# 12v-driver.net
KiCad netlist of a schematic drawn in EAGLE
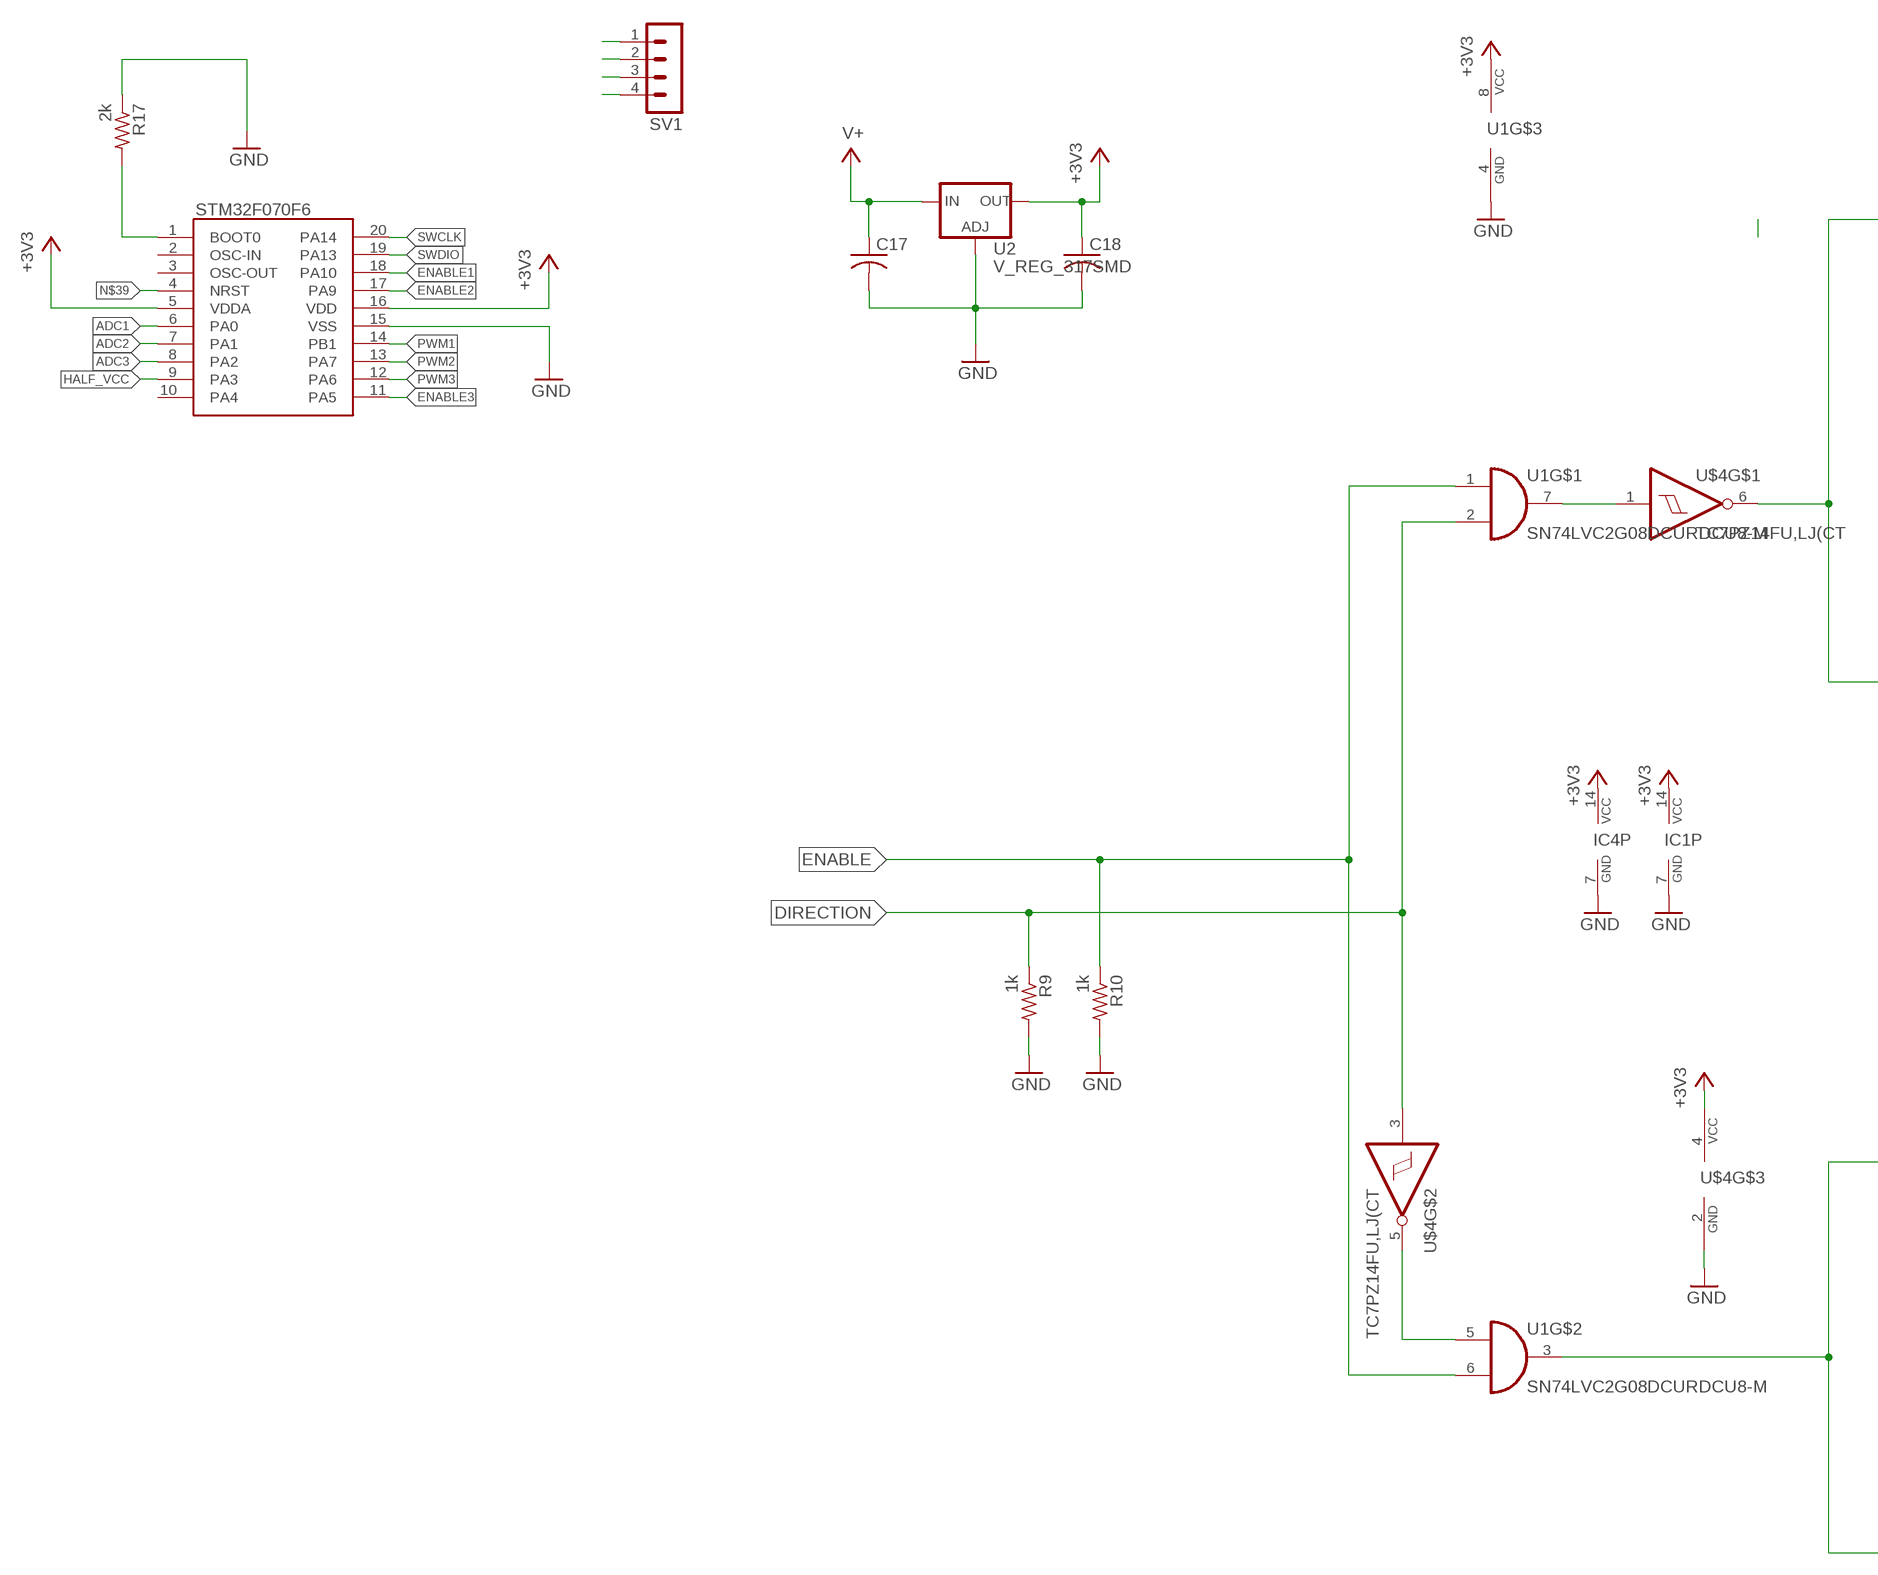
[diagram p0: schematic, sheet 1, part 1 of 2]
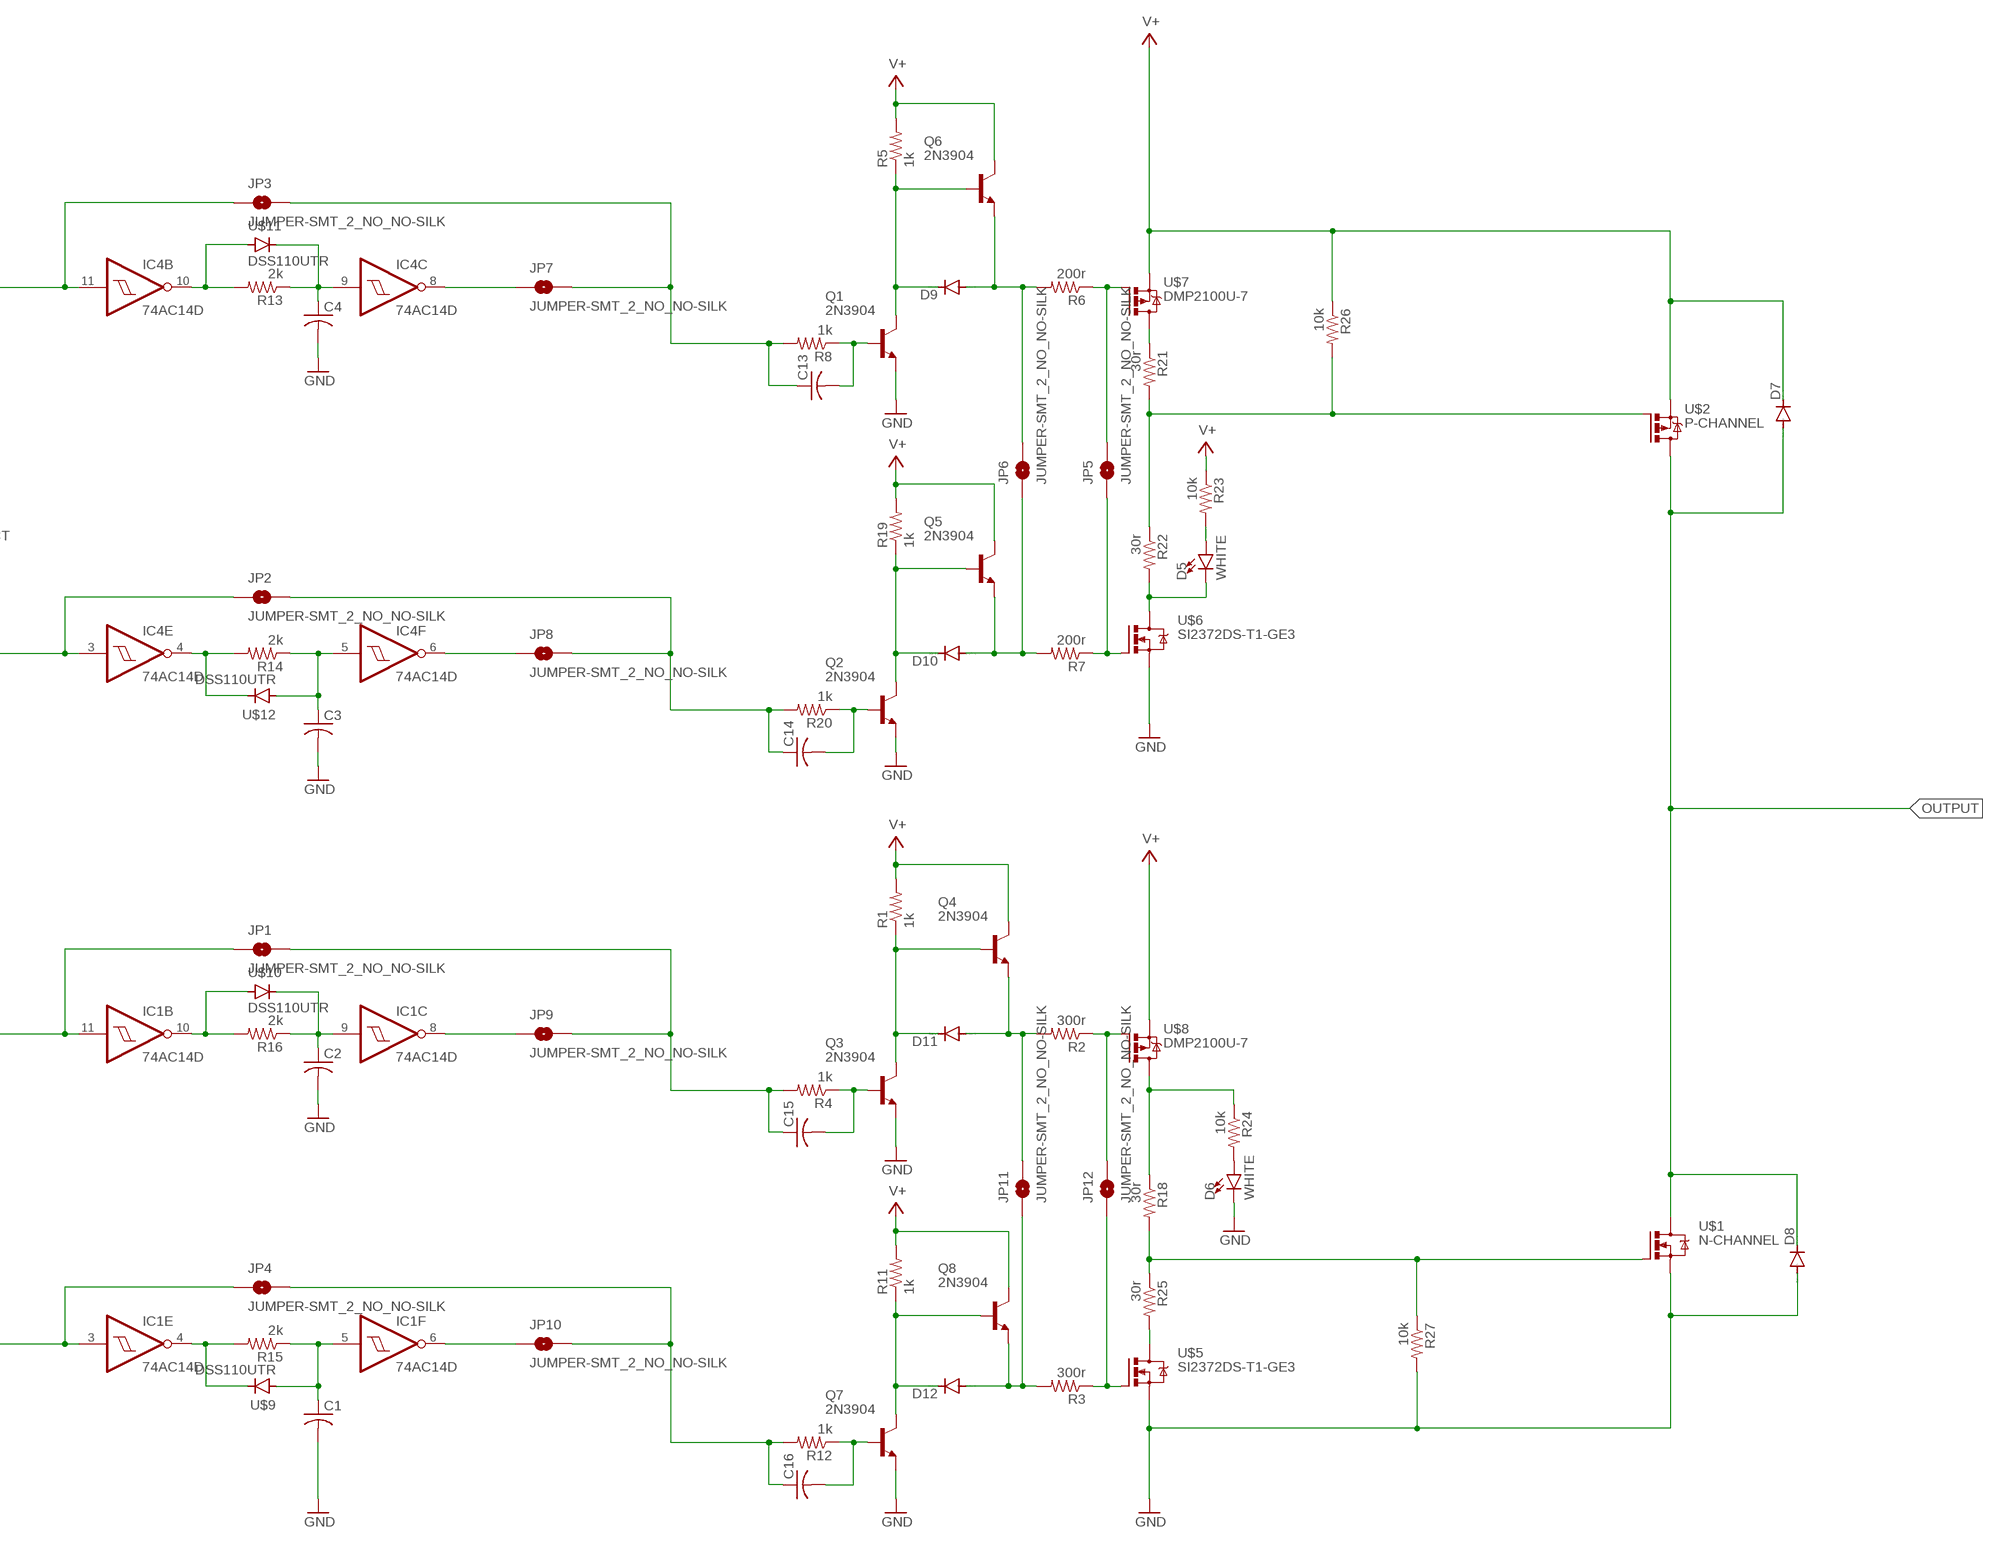
[diagram p1: schematic, sheet 1, part 2 of 2]

(export (version "E")
  (design (tool "Eeschema 10.0.6"))
  (components
    (comp (ref "C1")
      (value "C-USC0603")
      (footprint "eagle-import:C0603")
      (libsource (lib "eagle-import") (part "C-USC0603"))
    )
    (comp (ref "C2")
      (value "C-USC0603")
      (footprint "eagle-import:C0603")
      (libsource (lib "eagle-import") (part "C-USC0603"))
    )
    (comp (ref "C3")
      (value "C-USC0603")
      (footprint "eagle-import:C0603")
      (libsource (lib "eagle-import") (part "C-USC0603"))
    )
    (comp (ref "C4")
      (value "C-USC0603")
      (footprint "eagle-import:C0603")
      (libsource (lib "eagle-import") (part "C-USC0603"))
    )
    (comp (ref "C13")
      (value "C-USC0603")
      (footprint "eagle-import:C0603")
      (libsource (lib "eagle-import") (part "C-USC0603"))
    )
    (comp (ref "C14")
      (value "C-USC0603")
      (footprint "eagle-import:C0603")
      (libsource (lib "eagle-import") (part "C-USC0603"))
    )
    (comp (ref "C15")
      (value "C-USC0603")
      (footprint "eagle-import:C0603")
      (libsource (lib "eagle-import") (part "C-USC0603"))
    )
    (comp (ref "C16")
      (value "C-USC0603")
      (footprint "eagle-import:C0603")
      (libsource (lib "eagle-import") (part "C-USC0603"))
    )
    (comp (ref "C17")
      (value "C-US075-032X103")
      (footprint "eagle-import:C075-032X103")
      (libsource (lib "eagle-import") (part "C-US075-032X103"))
    )
    (comp (ref "C18")
      (value "C-US075-032X103")
      (footprint "eagle-import:C075-032X103")
      (libsource (lib "eagle-import") (part "C-US075-032X103"))
    )
    (comp (ref "D5")
      (value "WHITE")
      (footprint "eagle-import:LED-1206")
      (libsource (lib "eagle-import") (part "LED-WHITE1206"))
    )
    (comp (ref "D6")
      (value "WHITE")
      (footprint "eagle-import:LED-1206")
      (libsource (lib "eagle-import") (part "LED-WHITE1206"))
    )
    (comp (ref "D7")
      (value "DIODE-DO-214AC")
      (footprint "eagle-import:DO-214AC")
      (libsource (lib "eagle-import") (part "DIODE-DO-214AC"))
    )
    (comp (ref "D8")
      (value "DIODE-DO-214AC")
      (footprint "eagle-import:DO-214AC")
      (libsource (lib "eagle-import") (part "DIODE-DO-214AC"))
    )
    (comp (ref "D9")
      (value "DIODE-DO-214AC")
      (footprint "eagle-import:DO-214AC")
      (libsource (lib "eagle-import") (part "DIODE-DO-214AC"))
    )
    (comp (ref "D10")
      (value "DIODE-DO-214AC")
      (footprint "eagle-import:DO-214AC")
      (libsource (lib "eagle-import") (part "DIODE-DO-214AC"))
    )
    (comp (ref "D11")
      (value "DIODE-DO-214AC")
      (footprint "eagle-import:DO-214AC")
      (libsource (lib "eagle-import") (part "DIODE-DO-214AC"))
    )
    (comp (ref "D12")
      (value "DIODE-DO-214AC")
      (footprint "eagle-import:DO-214AC")
      (libsource (lib "eagle-import") (part "DIODE-DO-214AC"))
    )
    (comp (ref "IC1")
      (value "74AC14D")
      (footprint "eagle-import:SO14")
      (libsource (lib "eagle-import") (part "7414DAC"))
    )
    (comp (ref "IC4")
      (value "74AC14D")
      (footprint "eagle-import:SO14")
      (libsource (lib "eagle-import") (part "7414DAC"))
    )
    (comp (ref "JP1")
      (value "JUMPER-SMT_2_NO_NO-SILK")
      (footprint "eagle-import:SMT-JUMPER_2_NO_NO-SILK")
      (libsource (lib "eagle-import") (part "JUMPER-SMT_2_NO_NO-SILK"))
    )
    (comp (ref "JP2")
      (value "JUMPER-SMT_2_NO_NO-SILK")
      (footprint "eagle-import:SMT-JUMPER_2_NO_NO-SILK")
      (libsource (lib "eagle-import") (part "JUMPER-SMT_2_NO_NO-SILK"))
    )
    (comp (ref "JP3")
      (value "JUMPER-SMT_2_NO_NO-SILK")
      (footprint "eagle-import:SMT-JUMPER_2_NO_NO-SILK")
      (libsource (lib "eagle-import") (part "JUMPER-SMT_2_NO_NO-SILK"))
    )
    (comp (ref "JP4")
      (value "JUMPER-SMT_2_NO_NO-SILK")
      (footprint "eagle-import:SMT-JUMPER_2_NO_NO-SILK")
      (libsource (lib "eagle-import") (part "JUMPER-SMT_2_NO_NO-SILK"))
    )
    (comp (ref "JP5")
      (value "JUMPER-SMT_2_NO_NO-SILK")
      (footprint "eagle-import:SMT-JUMPER_2_NO_NO-SILK")
      (libsource (lib "eagle-import") (part "JUMPER-SMT_2_NO_NO-SILK"))
    )
    (comp (ref "JP6")
      (value "JUMPER-SMT_2_NO_NO-SILK")
      (footprint "eagle-import:SMT-JUMPER_2_NO_NO-SILK")
      (libsource (lib "eagle-import") (part "JUMPER-SMT_2_NO_NO-SILK"))
    )
    (comp (ref "JP7")
      (value "JUMPER-SMT_2_NO_NO-SILK")
      (footprint "eagle-import:SMT-JUMPER_2_NO_NO-SILK")
      (libsource (lib "eagle-import") (part "JUMPER-SMT_2_NO_NO-SILK"))
    )
    (comp (ref "JP8")
      (value "JUMPER-SMT_2_NO_NO-SILK")
      (footprint "eagle-import:SMT-JUMPER_2_NO_NO-SILK")
      (libsource (lib "eagle-import") (part "JUMPER-SMT_2_NO_NO-SILK"))
    )
    (comp (ref "JP9")
      (value "JUMPER-SMT_2_NO_NO-SILK")
      (footprint "eagle-import:SMT-JUMPER_2_NO_NO-SILK")
      (libsource (lib "eagle-import") (part "JUMPER-SMT_2_NO_NO-SILK"))
    )
    (comp (ref "JP10")
      (value "JUMPER-SMT_2_NO_NO-SILK")
      (footprint "eagle-import:SMT-JUMPER_2_NO_NO-SILK")
      (libsource (lib "eagle-import") (part "JUMPER-SMT_2_NO_NO-SILK"))
    )
    (comp (ref "JP11")
      (value "JUMPER-SMT_2_NO_NO-SILK")
      (footprint "eagle-import:SMT-JUMPER_2_NO_NO-SILK")
      (libsource (lib "eagle-import") (part "JUMPER-SMT_2_NO_NO-SILK"))
    )
    (comp (ref "JP12")
      (value "JUMPER-SMT_2_NO_NO-SILK")
      (footprint "eagle-import:SMT-JUMPER_2_NO_NO-SILK")
      (libsource (lib "eagle-import") (part "JUMPER-SMT_2_NO_NO-SILK"))
    )
    (comp (ref "Q1")
      (value "2N3904")
      (footprint "eagle-import:TO-92")
      (libsource (lib "eagle-import") (part "2N3904"))
    )
    (comp (ref "Q2")
      (value "2N3904")
      (footprint "eagle-import:TO-92")
      (libsource (lib "eagle-import") (part "2N3904"))
    )
    (comp (ref "Q3")
      (value "2N3904")
      (footprint "eagle-import:TO-92")
      (libsource (lib "eagle-import") (part "2N3904"))
    )
    (comp (ref "Q4")
      (value "2N3904")
      (footprint "eagle-import:TO-92")
      (libsource (lib "eagle-import") (part "2N3904"))
    )
    (comp (ref "Q5")
      (value "2N3904")
      (footprint "eagle-import:TO-92")
      (libsource (lib "eagle-import") (part "2N3904"))
    )
    (comp (ref "Q6")
      (value "2N3904")
      (footprint "eagle-import:TO-92")
      (libsource (lib "eagle-import") (part "2N3904"))
    )
    (comp (ref "Q7")
      (value "2N3904")
      (footprint "eagle-import:TO-92")
      (libsource (lib "eagle-import") (part "2N3904"))
    )
    (comp (ref "Q8")
      (value "2N3904")
      (footprint "eagle-import:TO-92")
      (libsource (lib "eagle-import") (part "2N3904"))
    )
    (comp (ref "R1")
      (value "1k")
      (footprint "eagle-import:R0603")
      (libsource (lib "eagle-import") (part "R-US_R0603"))
    )
    (comp (ref "R2")
      (value "300r")
      (footprint "eagle-import:R0603")
      (libsource (lib "eagle-import") (part "R-US_R0603"))
    )
    (comp (ref "R3")
      (value "300r")
      (footprint "eagle-import:R0603")
      (libsource (lib "eagle-import") (part "R-US_R0603"))
    )
    (comp (ref "R4")
      (value "1k")
      (footprint "eagle-import:R0603")
      (libsource (lib "eagle-import") (part "R-US_R0603"))
    )
    (comp (ref "R5")
      (value "1k")
      (footprint "eagle-import:R0603")
      (libsource (lib "eagle-import") (part "R-US_R0603"))
    )
    (comp (ref "R6")
      (value "200r")
      (footprint "eagle-import:R0603")
      (libsource (lib "eagle-import") (part "R-US_R0603"))
    )
    (comp (ref "R7")
      (value "200r")
      (footprint "eagle-import:R0603")
      (libsource (lib "eagle-import") (part "R-US_R0603"))
    )
    (comp (ref "R8")
      (value "1k")
      (footprint "eagle-import:R0603")
      (libsource (lib "eagle-import") (part "R-US_R0603"))
    )
    (comp (ref "R9")
      (value "1k")
      (footprint "eagle-import:R0603")
      (libsource (lib "eagle-import") (part "R-US_R0603"))
    )
    (comp (ref "R10")
      (value "1k")
      (footprint "eagle-import:R0603")
      (libsource (lib "eagle-import") (part "R-US_R0603"))
    )
    (comp (ref "R11")
      (value "1k")
      (footprint "eagle-import:R0603")
      (libsource (lib "eagle-import") (part "R-US_R0603"))
    )
    (comp (ref "R12")
      (value "1k")
      (footprint "eagle-import:R0603")
      (libsource (lib "eagle-import") (part "R-US_R0603"))
    )
    (comp (ref "R13")
      (value "2k")
      (footprint "eagle-import:R0603")
      (libsource (lib "eagle-import") (part "R-US_R0603"))
    )
    (comp (ref "R14")
      (value "2k")
      (footprint "eagle-import:R0603")
      (libsource (lib "eagle-import") (part "R-US_R0603"))
    )
    (comp (ref "R15")
      (value "2k")
      (footprint "eagle-import:R0603")
      (libsource (lib "eagle-import") (part "R-US_R0603"))
    )
    (comp (ref "R16")
      (value "2k")
      (footprint "eagle-import:R0603")
      (libsource (lib "eagle-import") (part "R-US_R0603"))
    )
    (comp (ref "R17")
      (value "2k")
      (footprint "eagle-import:R0603")
      (libsource (lib "eagle-import") (part "R-US_R0603"))
    )
    (comp (ref "R18")
      (value "30r")
      (footprint "eagle-import:R0603")
      (libsource (lib "eagle-import") (part "R-US_R0603"))
    )
    (comp (ref "R19")
      (value "1k")
      (footprint "eagle-import:R0603")
      (libsource (lib "eagle-import") (part "R-US_R0603"))
    )
    (comp (ref "R20")
      (value "1k")
      (footprint "eagle-import:R0603")
      (libsource (lib "eagle-import") (part "R-US_R0603"))
    )
    (comp (ref "R21")
      (value "30r")
      (footprint "eagle-import:R0603")
      (libsource (lib "eagle-import") (part "R-US_R0603"))
    )
    (comp (ref "R22")
      (value "30r")
      (footprint "eagle-import:R0603")
      (libsource (lib "eagle-import") (part "R-US_R0603"))
    )
    (comp (ref "R23")
      (value "10k")
      (footprint "eagle-import:R0603")
      (libsource (lib "eagle-import") (part "R-US_R0603"))
    )
    (comp (ref "R24")
      (value "10k")
      (footprint "eagle-import:R0603")
      (libsource (lib "eagle-import") (part "R-US_R0603"))
    )
    (comp (ref "R25")
      (value "30r")
      (footprint "eagle-import:R0603")
      (libsource (lib "eagle-import") (part "R-US_R0603"))
    )
    (comp (ref "R26")
      (value "10k")
      (footprint "eagle-import:R0603")
      (libsource (lib "eagle-import") (part "R-US_R0603"))
    )
    (comp (ref "R27")
      (value "10k")
      (footprint "eagle-import:R0603")
      (libsource (lib "eagle-import") (part "R-US_R0603"))
    )
    (comp (ref "SV1")
      (value "MA04-1")
      (footprint "eagle-import:MA04-1")
      (libsource (lib "eagle-import") (part "MA04-1"))
    )
    (comp (ref "U$1")
      (value "N-CHANNEL")
      (footprint "eagle-import:TO247BV")
      (libsource (lib "eagle-import") (part "N-CHANNEL"))
    )
    (comp (ref "U$2")
      (value "P-CHANNEL")
      (footprint "eagle-import:TO247BV")
      (libsource (lib "eagle-import") (part "P-CHANNEL"))
    )
    (comp (ref "U$3")
      (value "STM32F070F6P6TR")
      (footprint "eagle-import:TSSOP20")
      (libsource (lib "eagle-import") (part "STM32F070F6P6TR"))
    )
    (comp (ref "U$4")
      (value "TC7PZ14FU,LJ(CT")
      (footprint "eagle-import:SOT-363___(US6)")
      (libsource (lib "eagle-import") (part "TC7PZ14FU,LJ(CT"))
    )
    (comp (ref "U$5")
      (value "SI2372DS-T1-GE3")
      (footprint "eagle-import:SOT-23")
      (libsource (lib "eagle-import") (part "SI2372DS-T1-GE3"))
    )
    (comp (ref "U$6")
      (value "SI2372DS-T1-GE3")
      (footprint "eagle-import:SOT-23")
      (libsource (lib "eagle-import") (part "SI2372DS-T1-GE3"))
    )
    (comp (ref "U$7")
      (value "DMP2100U-7")
      (footprint "eagle-import:SOT-23")
      (libsource (lib "eagle-import") (part "DMP2100U-7"))
    )
    (comp (ref "U$8")
      (value "DMP2100U-7")
      (footprint "eagle-import:SOT-23")
      (libsource (lib "eagle-import") (part "DMP2100U-7"))
    )
    (comp (ref "U$9")
      (value "DSS110UTR")
      (footprint "eagle-import:SOD123FL")
      (libsource (lib "eagle-import") (part "DSS110UTR"))
    )
    (comp (ref "U$10")
      (value "DSS110UTR")
      (footprint "eagle-import:SOD123FL")
      (libsource (lib "eagle-import") (part "DSS110UTR"))
    )
    (comp (ref "U$11")
      (value "DSS110UTR")
      (footprint "eagle-import:SOD123FL")
      (libsource (lib "eagle-import") (part "DSS110UTR"))
    )
    (comp (ref "U$12")
      (value "DSS110UTR")
      (footprint "eagle-import:SOD123FL")
      (libsource (lib "eagle-import") (part "DSS110UTR"))
    )
    (comp (ref "U1")
      (value "SN74LVC2G08DCURDCU8-M")
      (footprint "eagle-import:DCU8-M")
      (fields
        (field (name "GENERIC_PART_NUMBER") "SN74LVC2G08")
        (field (name "MANUFACTURER") "Texas Instruments")
        (field (name "MANUFACTURER_PART_NUMBER") "SN74LVC2G08DCUR")
      )
      (libsource (lib "eagle-import") (part "SN74LVC2G08DCURDCU8-M"))
    )
    (comp (ref "U2")
      (value "V_REG_317SMD")
      (footprint "eagle-import:SOT223")
      (libsource (lib "eagle-import") (part "V_REG_317SMD"))
    )
  )
  (nets
    (net (code "1") (name "+3V3") (class "Default")
      (node (ref "C18") (pin "1") (pinfunction "1_1") (pintype "passive"))
      (node (ref "IC1") (pin "14") (pinfunction "VCC_14") (pintype "power_in"))
      (node (ref "IC4") (pin "14") (pinfunction "VCC_14") (pintype "power_in"))
      (node (ref "U$3") (pin "16") (pinfunction "VDD_16") (pintype "bidirectional"))
      (node (ref "U$3") (pin "5") (pinfunction "VDDA_5") (pintype "bidirectional"))
      (node (ref "U$4") (pin "4") (pinfunction "VCC_4") (pintype "power_in"))
      (node (ref "U1") (pin "8") (pinfunction "VCC_8") (pintype "power_in"))
      (node (ref "U2") (pin "2") (pinfunction "OUT_2") (pintype "output"))
    )
    (net (code "2") (name "ADC1") (class "Default")
      (node (ref "U$3") (pin "6") (pinfunction "PA0_6") (pintype "bidirectional"))
    )
    (net (code "3") (name "ADC2") (class "Default")
      (node (ref "U$3") (pin "7") (pinfunction "PA1_7") (pintype "bidirectional"))
    )
    (net (code "4") (name "ADC3") (class "Default")
      (node (ref "U$3") (pin "8") (pinfunction "PA2_8") (pintype "bidirectional"))
    )
    (net (code "5") (name "DIRECTION") (class "Default")
      (node (ref "R9") (pin "1") (pinfunction "1_1") (pintype "passive"))
      (node (ref "U$4") (pin "3") (pinfunction "I_3") (pintype "input"))
      (node (ref "U1") (pin "2") (pinfunction "I1_2") (pintype "input"))
    )
    (net (code "6") (name "ENABLE") (class "Default")
      (node (ref "R10") (pin "1") (pinfunction "1_1") (pintype "passive"))
      (node (ref "U1") (pin "1") (pinfunction "I0_1") (pintype "input"))
      (node (ref "U1") (pin "6") (pinfunction "I1_6") (pintype "input"))
    )
    (net (code "7") (name "ENABLE1") (class "Default")
      (node (ref "U$3") (pin "18") (pinfunction "PA10_18") (pintype "bidirectional"))
    )
    (net (code "8") (name "ENABLE2") (class "Default")
      (node (ref "U$3") (pin "17") (pinfunction "PA9_17") (pintype "bidirectional"))
    )
    (net (code "9") (name "ENABLE3") (class "Default")
      (node (ref "U$3") (pin "11") (pinfunction "PA5_11") (pintype "bidirectional"))
    )
    (net (code "10") (name "GND") (class "Default")
      (node (ref "C1") (pin "2") (pinfunction "2_2") (pintype "passive"))
      (node (ref "C17") (pin "2") (pinfunction "2_2") (pintype "passive"))
      (node (ref "C18") (pin "2") (pinfunction "2_2") (pintype "passive"))
      (node (ref "C2") (pin "2") (pinfunction "2_2") (pintype "passive"))
      (node (ref "C3") (pin "2") (pinfunction "2_2") (pintype "passive"))
      (node (ref "C4") (pin "2") (pinfunction "2_2") (pintype "passive"))
      (node (ref "D6") (pin "C") (pinfunction "C_C") (pintype "passive"))
      (node (ref "D8") (pin "A") (pinfunction "A_A") (pintype "passive"))
      (node (ref "IC1") (pin "7") (pinfunction "GND_7") (pintype "power_in"))
      (node (ref "IC4") (pin "7") (pinfunction "GND_7") (pintype "power_in"))
      (node (ref "Q1") (pin "E") (pinfunction "E_E") (pintype "passive"))
      (node (ref "Q2") (pin "E") (pinfunction "E_E") (pintype "passive"))
      (node (ref "Q3") (pin "E") (pinfunction "E_E") (pintype "passive"))
      (node (ref "Q7") (pin "E") (pinfunction "E_E") (pintype "passive"))
      (node (ref "R10") (pin "2") (pinfunction "2_2") (pintype "passive"))
      (node (ref "R17") (pin "1") (pinfunction "1_1") (pintype "passive"))
      (node (ref "R27") (pin "2") (pinfunction "2_2") (pintype "passive"))
      (node (ref "R9") (pin "2") (pinfunction "2_2") (pintype "passive"))
      (node (ref "U$1") (pin "S") (pinfunction "S_S") (pintype "passive"))
      (node (ref "U$3") (pin "15") (pinfunction "VSS_15") (pintype "bidirectional"))
      (node (ref "U$4") (pin "2") (pinfunction "GND_2") (pintype "power_in"))
      (node (ref "U$5") (pin "2") (pinfunction "S_2") (pintype "passive"))
      (node (ref "U$6") (pin "2") (pinfunction "S_2") (pintype "passive"))
      (node (ref "U1") (pin "4") (pinfunction "GND_4") (pintype "power_in"))
      (node (ref "U2") (pin "1") (pinfunction "ADJ_1") (pintype "input"))
    )
    (net (code "11") (name "HALF_VCC") (class "Default")
      (node (ref "U$3") (pin "9") (pinfunction "PA3_9") (pintype "bidirectional"))
    )
    (net (code "12") (name "N$39") (class "Default")
      (node (ref "U$3") (pin "4") (pinfunction "NRST_4") (pintype "bidirectional"))
    )
    (net (code "13") (name "Net-(C13-Pad1)") (class "Default")
      (node (ref "C13") (pin "1") (pinfunction "1_1") (pintype "passive"))
      (node (ref "JP3") (pin "2") (pinfunction "2_2") (pintype "passive"))
      (node (ref "JP7") (pin "2") (pinfunction "2_2") (pintype "passive"))
      (node (ref "R8") (pin "2") (pinfunction "2_2") (pintype "passive"))
    )
    (net (code "14") (name "Net-(C13-Pad2)") (class "Default")
      (node (ref "C13") (pin "2") (pinfunction "2_2") (pintype "passive"))
      (node (ref "Q1") (pin "B") (pinfunction "B_B") (pintype "passive"))
      (node (ref "R8") (pin "1") (pinfunction "1_1") (pintype "passive"))
    )
    (net (code "15") (name "Net-(C14-Pad1)") (class "Default")
      (node (ref "C14") (pin "1") (pinfunction "1_1") (pintype "passive"))
      (node (ref "JP2") (pin "2") (pinfunction "2_2") (pintype "passive"))
      (node (ref "JP8") (pin "2") (pinfunction "2_2") (pintype "passive"))
      (node (ref "R20") (pin "2") (pinfunction "2_2") (pintype "passive"))
    )
    (net (code "16") (name "Net-(C14-Pad2)") (class "Default")
      (node (ref "C14") (pin "2") (pinfunction "2_2") (pintype "passive"))
      (node (ref "Q2") (pin "B") (pinfunction "B_B") (pintype "passive"))
      (node (ref "R20") (pin "1") (pinfunction "1_1") (pintype "passive"))
    )
    (net (code "17") (name "Net-(C15-Pad1)") (class "Default")
      (node (ref "C15") (pin "1") (pinfunction "1_1") (pintype "passive"))
      (node (ref "JP1") (pin "2") (pinfunction "2_2") (pintype "passive"))
      (node (ref "JP9") (pin "2") (pinfunction "2_2") (pintype "passive"))
      (node (ref "R4") (pin "2") (pinfunction "2_2") (pintype "passive"))
    )
    (net (code "18") (name "Net-(C15-Pad2)") (class "Default")
      (node (ref "C15") (pin "2") (pinfunction "2_2") (pintype "passive"))
      (node (ref "Q3") (pin "B") (pinfunction "B_B") (pintype "passive"))
      (node (ref "R4") (pin "1") (pinfunction "1_1") (pintype "passive"))
    )
    (net (code "19") (name "Net-(C16-Pad1)") (class "Default")
      (node (ref "C16") (pin "1") (pinfunction "1_1") (pintype "passive"))
      (node (ref "JP10") (pin "2") (pinfunction "2_2") (pintype "passive"))
      (node (ref "JP4") (pin "2") (pinfunction "2_2") (pintype "passive"))
      (node (ref "R12") (pin "2") (pinfunction "2_2") (pintype "passive"))
    )
    (net (code "20") (name "Net-(C16-Pad2)") (class "Default")
      (node (ref "C16") (pin "2") (pinfunction "2_2") (pintype "passive"))
      (node (ref "Q7") (pin "B") (pinfunction "B_B") (pintype "passive"))
      (node (ref "R12") (pin "1") (pinfunction "1_1") (pintype "passive"))
    )
    (net (code "21") (name "Net-(D5-PadA)") (class "Default")
      (node (ref "D5") (pin "A") (pinfunction "A_A") (pintype "passive"))
      (node (ref "R23") (pin "2") (pinfunction "2_2") (pintype "passive"))
    )
    (net (code "22") (name "Net-(D6-PadA)") (class "Default")
      (node (ref "D6") (pin "A") (pinfunction "A_A") (pintype "passive"))
      (node (ref "R24") (pin "2") (pinfunction "2_2") (pintype "passive"))
    )
    (net (code "23") (name "Net-(D9-PadA)") (class "Default")
      (node (ref "D9") (pin "A") (pinfunction "A_A") (pintype "passive"))
      (node (ref "JP6") (pin "2") (pinfunction "2_2") (pintype "passive"))
      (node (ref "Q6") (pin "E") (pinfunction "E_E") (pintype "passive"))
      (node (ref "R6") (pin "2") (pinfunction "2_2") (pintype "passive"))
    )
    (net (code "24") (name "Net-(D9-PadC)") (class "Default")
      (node (ref "D9") (pin "C") (pinfunction "C_C") (pintype "passive"))
      (node (ref "Q1") (pin "C") (pinfunction "C_C") (pintype "passive"))
      (node (ref "Q6") (pin "B") (pinfunction "B_B") (pintype "passive"))
      (node (ref "R5") (pin "1") (pinfunction "1_1") (pintype "passive"))
    )
    (net (code "25") (name "Net-(D10-PadA)") (class "Default")
      (node (ref "D10") (pin "A") (pinfunction "A_A") (pintype "passive"))
      (node (ref "JP6") (pin "1") (pinfunction "1_1") (pintype "passive"))
      (node (ref "Q5") (pin "E") (pinfunction "E_E") (pintype "passive"))
      (node (ref "R7") (pin "2") (pinfunction "2_2") (pintype "passive"))
    )
    (net (code "26") (name "Net-(D10-PadC)") (class "Default")
      (node (ref "D10") (pin "C") (pinfunction "C_C") (pintype "passive"))
      (node (ref "Q2") (pin "C") (pinfunction "C_C") (pintype "passive"))
      (node (ref "Q5") (pin "B") (pinfunction "B_B") (pintype "passive"))
      (node (ref "R19") (pin "1") (pinfunction "1_1") (pintype "passive"))
    )
    (net (code "27") (name "Net-(D11-PadA)") (class "Default")
      (node (ref "D11") (pin "A") (pinfunction "A_A") (pintype "passive"))
      (node (ref "JP11") (pin "2") (pinfunction "2_2") (pintype "passive"))
      (node (ref "Q4") (pin "E") (pinfunction "E_E") (pintype "passive"))
      (node (ref "R2") (pin "2") (pinfunction "2_2") (pintype "passive"))
    )
    (net (code "28") (name "Net-(D11-PadC)") (class "Default")
      (node (ref "D11") (pin "C") (pinfunction "C_C") (pintype "passive"))
      (node (ref "Q3") (pin "C") (pinfunction "C_C") (pintype "passive"))
      (node (ref "Q4") (pin "B") (pinfunction "B_B") (pintype "passive"))
      (node (ref "R1") (pin "1") (pinfunction "1_1") (pintype "passive"))
    )
    (net (code "29") (name "Net-(D12-PadA)") (class "Default")
      (node (ref "D12") (pin "A") (pinfunction "A_A") (pintype "passive"))
      (node (ref "JP11") (pin "1") (pinfunction "1_1") (pintype "passive"))
      (node (ref "Q8") (pin "E") (pinfunction "E_E") (pintype "passive"))
      (node (ref "R3") (pin "2") (pinfunction "2_2") (pintype "passive"))
    )
    (net (code "30") (name "Net-(D12-PadC)") (class "Default")
      (node (ref "D12") (pin "C") (pinfunction "C_C") (pintype "passive"))
      (node (ref "Q7") (pin "C") (pinfunction "C_C") (pintype "passive"))
      (node (ref "Q8") (pin "B") (pinfunction "B_B") (pintype "passive"))
      (node (ref "R11") (pin "1") (pinfunction "1_1") (pintype "passive"))
    )
    (net (code "31") (name "Net-(IC1B-I)") (class "Default")
      (node (ref "IC1") (pin "11") (pinfunction "I_11") (pintype "input"))
      (node (ref "IC1") (pin "3") (pinfunction "I_3") (pintype "input"))
      (node (ref "JP1") (pin "1") (pinfunction "1_1") (pintype "passive"))
      (node (ref "JP4") (pin "1") (pinfunction "1_1") (pintype "passive"))
      (node (ref "U1") (pin "3") (pinfunction "O_3") (pintype "output"))
    )
    (net (code "32") (name "Net-(IC1B-O)") (class "Default")
      (node (ref "IC1") (pin "10") (pinfunction "O_10") (pintype "output"))
      (node (ref "R16") (pin "2") (pinfunction "2_2") (pintype "passive"))
      (node (ref "U$10") (pin "A") (pinfunction "A_A") (pintype "passive"))
    )
    (net (code "33") (name "Net-(IC1C-I)") (class "Default")
      (node (ref "C2") (pin "1") (pinfunction "1_1") (pintype "passive"))
      (node (ref "IC1") (pin "9") (pinfunction "I_9") (pintype "input"))
      (node (ref "R16") (pin "1") (pinfunction "1_1") (pintype "passive"))
      (node (ref "U$10") (pin "C") (pinfunction "C_C") (pintype "passive"))
    )
    (net (code "34") (name "Net-(IC1C-O)") (class "Default")
      (node (ref "IC1") (pin "8") (pinfunction "O_8") (pintype "output"))
      (node (ref "JP9") (pin "1") (pinfunction "1_1") (pintype "passive"))
    )
    (net (code "35") (name "Net-(IC1E-O)") (class "Default")
      (node (ref "IC1") (pin "4") (pinfunction "O_4") (pintype "output"))
      (node (ref "R15") (pin "2") (pinfunction "2_2") (pintype "passive"))
      (node (ref "U$9") (pin "C") (pinfunction "C_C") (pintype "passive"))
    )
    (net (code "36") (name "Net-(IC1F-I)") (class "Default")
      (node (ref "C1") (pin "1") (pinfunction "1_1") (pintype "passive"))
      (node (ref "IC1") (pin "5") (pinfunction "I_5") (pintype "input"))
      (node (ref "R15") (pin "1") (pinfunction "1_1") (pintype "passive"))
      (node (ref "U$9") (pin "A") (pinfunction "A_A") (pintype "passive"))
    )
    (net (code "37") (name "Net-(IC1F-O)") (class "Default")
      (node (ref "IC1") (pin "6") (pinfunction "O_6") (pintype "output"))
      (node (ref "JP10") (pin "1") (pinfunction "1_1") (pintype "passive"))
    )
    (net (code "38") (name "Net-(IC4B-I)") (class "Default")
      (node (ref "IC4") (pin "11") (pinfunction "I_11") (pintype "input"))
      (node (ref "IC4") (pin "3") (pinfunction "I_3") (pintype "input"))
      (node (ref "JP2") (pin "1") (pinfunction "1_1") (pintype "passive"))
      (node (ref "JP3") (pin "1") (pinfunction "1_1") (pintype "passive"))
      (node (ref "U$4") (pin "6") (pinfunction "O_6") (pintype "output"))
    )
    (net (code "39") (name "Net-(IC4B-O)") (class "Default")
      (node (ref "IC4") (pin "10") (pinfunction "O_10") (pintype "output"))
      (node (ref "R13") (pin "2") (pinfunction "2_2") (pintype "passive"))
      (node (ref "U$11") (pin "A") (pinfunction "A_A") (pintype "passive"))
    )
    (net (code "40") (name "Net-(IC4C-I)") (class "Default")
      (node (ref "C4") (pin "1") (pinfunction "1_1") (pintype "passive"))
      (node (ref "IC4") (pin "9") (pinfunction "I_9") (pintype "input"))
      (node (ref "R13") (pin "1") (pinfunction "1_1") (pintype "passive"))
      (node (ref "U$11") (pin "C") (pinfunction "C_C") (pintype "passive"))
    )
    (net (code "41") (name "Net-(IC4C-O)") (class "Default")
      (node (ref "IC4") (pin "8") (pinfunction "O_8") (pintype "output"))
      (node (ref "JP7") (pin "1") (pinfunction "1_1") (pintype "passive"))
    )
    (net (code "42") (name "Net-(IC4E-O)") (class "Default")
      (node (ref "IC4") (pin "4") (pinfunction "O_4") (pintype "output"))
      (node (ref "R14") (pin "2") (pinfunction "2_2") (pintype "passive"))
      (node (ref "U$12") (pin "C") (pinfunction "C_C") (pintype "passive"))
    )
    (net (code "43") (name "Net-(IC4F-I)") (class "Default")
      (node (ref "C3") (pin "1") (pinfunction "1_1") (pintype "passive"))
      (node (ref "IC4") (pin "5") (pinfunction "I_5") (pintype "input"))
      (node (ref "R14") (pin "1") (pinfunction "1_1") (pintype "passive"))
      (node (ref "U$12") (pin "A") (pinfunction "A_A") (pintype "passive"))
    )
    (net (code "44") (name "Net-(IC4F-O)") (class "Default")
      (node (ref "IC4") (pin "6") (pinfunction "O_6") (pintype "output"))
      (node (ref "JP8") (pin "1") (pinfunction "1_1") (pintype "passive"))
    )
    (net (code "45") (name "Net-(R18-Pad2)") (class "Default")
      (node (ref "R18") (pin "2") (pinfunction "2_2") (pintype "passive"))
      (node (ref "R25") (pin "1") (pinfunction "1_1") (pintype "passive"))
      (node (ref "R27") (pin "1") (pinfunction "1_1") (pintype "passive"))
      (node (ref "U$1") (pin "G") (pinfunction "G_G") (pintype "passive"))
    )
    (net (code "46") (name "Net-(R21-Pad2)") (class "Default")
      (node (ref "R21") (pin "2") (pinfunction "2_2") (pintype "passive"))
      (node (ref "R22") (pin "1") (pinfunction "1_1") (pintype "passive"))
      (node (ref "R26") (pin "2") (pinfunction "2_2") (pintype "passive"))
      (node (ref "U$2") (pin "G") (pinfunction "G_G") (pintype "bidirectional"))
    )
    (net (code "47") (name "Net-(U$3-BOOT0)") (class "Default")
      (node (ref "R17") (pin "2") (pinfunction "2_2") (pintype "passive"))
      (node (ref "U$3") (pin "1") (pinfunction "BOOT0_1") (pintype "bidirectional"))
    )
    (net (code "48") (name "Net-(U$4A-I)") (class "Default")
      (node (ref "U$4") (pin "1") (pinfunction "I_1") (pintype "input"))
      (node (ref "U1") (pin "7") (pinfunction "O_7") (pintype "output"))
    )
    (net (code "49") (name "Net-(U$4B-O)") (class "Default")
      (node (ref "U$4") (pin "5") (pinfunction "O_5") (pintype "output"))
      (node (ref "U1") (pin "5") (pinfunction "I0_5") (pintype "input"))
    )
    (net (code "50") (name "Net-(U$5-D)") (class "Default")
      (node (ref "R25") (pin "2") (pinfunction "2_2") (pintype "passive"))
      (node (ref "U$5") (pin "3") (pinfunction "D_3") (pintype "passive"))
    )
    (net (code "51") (name "Net-(U$5-G)") (class "Default")
      (node (ref "JP12") (pin "1") (pinfunction "1_1") (pintype "passive"))
      (node (ref "R3") (pin "1") (pinfunction "1_1") (pintype "passive"))
      (node (ref "U$5") (pin "1") (pinfunction "G_1") (pintype "passive"))
    )
    (net (code "52") (name "Net-(U$6-D)") (class "Default")
      (node (ref "D5") (pin "C") (pinfunction "C_C") (pintype "passive"))
      (node (ref "R22") (pin "2") (pinfunction "2_2") (pintype "passive"))
      (node (ref "U$6") (pin "3") (pinfunction "D_3") (pintype "passive"))
    )
    (net (code "53") (name "Net-(U$6-G)") (class "Default")
      (node (ref "JP5") (pin "1") (pinfunction "1_1") (pintype "passive"))
      (node (ref "R7") (pin "1") (pinfunction "1_1") (pintype "passive"))
      (node (ref "U$6") (pin "1") (pinfunction "G_1") (pintype "passive"))
    )
    (net (code "54") (name "Net-(U$7-D)") (class "Default")
      (node (ref "R21") (pin "1") (pinfunction "1_1") (pintype "passive"))
      (node (ref "U$7") (pin "3") (pinfunction "D_3") (pintype "bidirectional"))
    )
    (net (code "55") (name "Net-(U$7-G)") (class "Default")
      (node (ref "JP5") (pin "2") (pinfunction "2_2") (pintype "passive"))
      (node (ref "R6") (pin "1") (pinfunction "1_1") (pintype "passive"))
      (node (ref "U$7") (pin "1") (pinfunction "G_1") (pintype "bidirectional"))
    )
    (net (code "56") (name "Net-(U$8-D)") (class "Default")
      (node (ref "R18") (pin "1") (pinfunction "1_1") (pintype "passive"))
      (node (ref "R24") (pin "1") (pinfunction "1_1") (pintype "passive"))
      (node (ref "U$8") (pin "3") (pinfunction "D_3") (pintype "bidirectional"))
    )
    (net (code "57") (name "Net-(U$8-G)") (class "Default")
      (node (ref "JP12") (pin "2") (pinfunction "2_2") (pintype "passive"))
      (node (ref "R2") (pin "1") (pinfunction "1_1") (pintype "passive"))
      (node (ref "U$8") (pin "1") (pinfunction "G_1") (pintype "bidirectional"))
    )
    (net (code "58") (name "OUTPUT") (class "Default")
      (node (ref "D7") (pin "A") (pinfunction "A_A") (pintype "passive"))
      (node (ref "D8") (pin "C") (pinfunction "C_C") (pintype "passive"))
      (node (ref "U$1") (pin "D") (pinfunction "D_D") (pintype "passive"))
      (node (ref "U$2") (pin "D") (pinfunction "D_D") (pintype "bidirectional"))
    )
    (net (code "59") (name "PWM1") (class "Default")
      (node (ref "U$3") (pin "14") (pinfunction "PB1_14") (pintype "bidirectional"))
    )
    (net (code "60") (name "PWM2") (class "Default")
      (node (ref "U$3") (pin "13") (pinfunction "PA7_13") (pintype "bidirectional"))
    )
    (net (code "61") (name "PWM3") (class "Default")
      (node (ref "U$3") (pin "12") (pinfunction "PA6_12") (pintype "bidirectional"))
    )
    (net (code "62") (name "SWCLK") (class "Default")
      (node (ref "U$3") (pin "20") (pinfunction "PA14_20") (pintype "bidirectional"))
    )
    (net (code "63") (name "SWDIO") (class "Default")
      (node (ref "U$3") (pin "19") (pinfunction "PA13_19") (pintype "bidirectional"))
    )
    (net (code "64") (name "V+") (class "Default")
      (node (ref "C17") (pin "1") (pinfunction "1_1") (pintype "passive"))
      (node (ref "D7") (pin "C") (pinfunction "C_C") (pintype "passive"))
      (node (ref "Q4") (pin "C") (pinfunction "C_C") (pintype "passive"))
      (node (ref "Q5") (pin "C") (pinfunction "C_C") (pintype "passive"))
      (node (ref "Q6") (pin "C") (pinfunction "C_C") (pintype "passive"))
      (node (ref "Q8") (pin "C") (pinfunction "C_C") (pintype "passive"))
      (node (ref "R1") (pin "2") (pinfunction "2_2") (pintype "passive"))
      (node (ref "R11") (pin "2") (pinfunction "2_2") (pintype "passive"))
      (node (ref "R19") (pin "2") (pinfunction "2_2") (pintype "passive"))
      (node (ref "R23") (pin "1") (pinfunction "1_1") (pintype "passive"))
      (node (ref "R26") (pin "1") (pinfunction "1_1") (pintype "passive"))
      (node (ref "R5") (pin "2") (pinfunction "2_2") (pintype "passive"))
      (node (ref "U$2") (pin "S") (pinfunction "S_S") (pintype "bidirectional"))
      (node (ref "U$7") (pin "2") (pinfunction "S_2") (pintype "bidirectional"))
      (node (ref "U$8") (pin "2") (pinfunction "S_2") (pintype "bidirectional"))
      (node (ref "U2") (pin "3") (pinfunction "IN_3") (pintype "input"))
    )
    (net (code "65") (name "unconnected-(SV1-Pad1)") (class "Default")
      (node (ref "SV1") (pin "1") (pinfunction "1_1") (pintype "passive"))
    )
    (net (code "66") (name "unconnected-(SV1-Pad2)") (class "Default")
      (node (ref "SV1") (pin "2") (pinfunction "2_2") (pintype "passive"))
    )
    (net (code "67") (name "unconnected-(SV1-Pad3)") (class "Default")
      (node (ref "SV1") (pin "3") (pinfunction "3_3") (pintype "passive"))
    )
    (net (code "68") (name "unconnected-(SV1-Pad4)") (class "Default")
      (node (ref "SV1") (pin "4") (pinfunction "4_4") (pintype "passive"))
    )
    (net (code "69") (name "unconnected-(U$3-OSC-IN-Pad2)") (class "Default")
      (node (ref "U$3") (pin "2") (pinfunction "OSC-IN_2") (pintype "bidirectional"))
    )
    (net (code "70") (name "unconnected-(U$3-OSC-OUT-Pad3)") (class "Default")
      (node (ref "U$3") (pin "3") (pinfunction "OSC-OUT_3") (pintype "bidirectional"))
    )
    (net (code "71") (name "unconnected-(U$3-PA4-Pad10)") (class "Default")
      (node (ref "U$3") (pin "10") (pinfunction "PA4_10") (pintype "bidirectional"))
    )
  )
)
